# Sensors_Test.net
KiCad netlist of a schematic drawn in Altium Designer
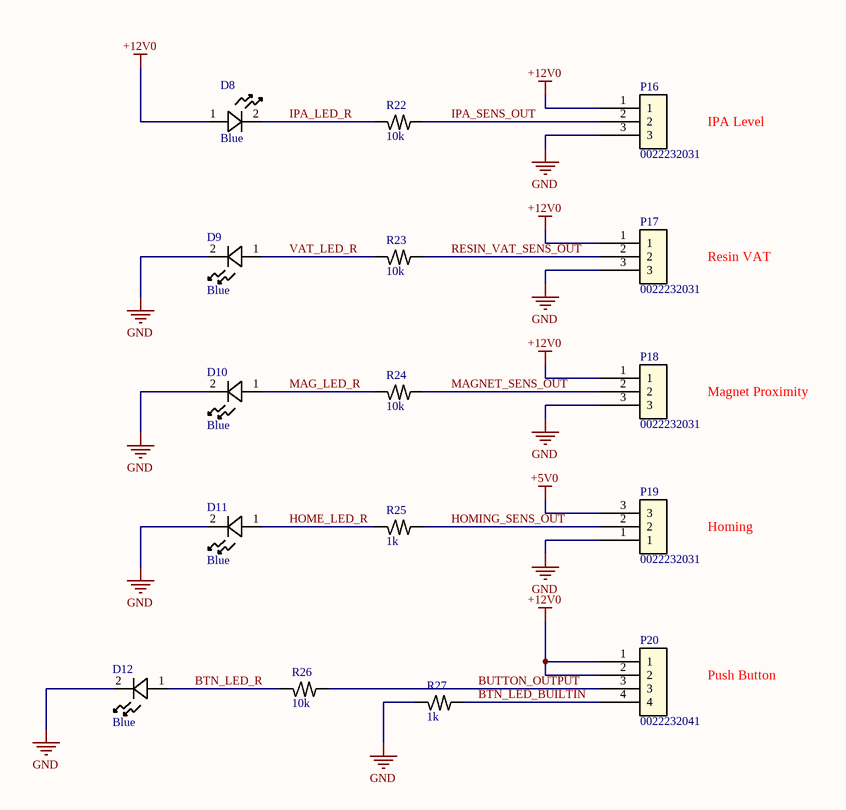
[diagram p0: Sensors Test.SchDoc]

(export (version "E")
  (design (tool "Eeschema 10.0.6"))
  (components
    (comp (ref "D8")
      (value "Blue")
      (footprint "LED0805 BLUE")
      (description "LED BLUE WATER CLEAR 0805 SMD")
      (fields (field (name "MF") "XINGLIGHT") (field (name "MP") "XL-TD2012UBC"))
      (libsource (lib "Components") (part "LED"))
    )
    (comp (ref "D9")
      (value "Blue")
      (footprint "LED0805 BLUE")
      (description "LED BLUE WATER CLEAR 0805 SMD")
      (fields (field (name "MF") "XINGLIGHT") (field (name "MP") "XL-TD2012UBC"))
      (libsource (lib "Components") (part "LED"))
    )
    (comp (ref "D10")
      (value "Blue")
      (footprint "LED0805 BLUE")
      (description "LED BLUE WATER CLEAR 0805 SMD")
      (fields (field (name "MF") "XINGLIGHT") (field (name "MP") "XL-TD2012UBC"))
      (libsource (lib "Components") (part "LED"))
    )
    (comp (ref "D11")
      (value "Blue")
      (footprint "LED0805 BLUE")
      (description "LED BLUE WATER CLEAR 0805 SMD")
      (fields (field (name "MF") "XINGLIGHT") (field (name "MP") "XL-TD2012UBC"))
      (libsource (lib "Components") (part "LED"))
    )
    (comp (ref "D12")
      (value "Blue")
      (footprint "LED0805 BLUE")
      (description "LED BLUE WATER CLEAR 0805 SMD")
      (fields (field (name "MF") "XINGLIGHT") (field (name "MP") "XL-TD2012UBC"))
      (libsource (lib "Components") (part "LED"))
    )
    (comp (ref "P16")
      (value "0022232031")
      (footprint "Signal3")
      (description "SignalConnector, 3 leads")
      (fields (field (name "MF") "Molex"))
      (libsource (lib "Connectors") (part "Signal3"))
    )
    (comp (ref "P17")
      (value "0022232031")
      (footprint "Signal3")
      (description "SignalConnector, 3 leads")
      (fields (field (name "MF") "Molex"))
      (libsource (lib "Connectors") (part "Signal3"))
    )
    (comp (ref "P18")
      (value "0022232031")
      (footprint "Signal3")
      (description "SignalConnector, 3 leads")
      (fields (field (name "MF") "Molex"))
      (libsource (lib "Connectors") (part "Signal3"))
    )
    (comp (ref "P19")
      (value "0022232031")
      (footprint "Signal3")
      (description "SignalConnector, 3 leads")
      (fields (field (name "MF") "Molex"))
      (libsource (lib "") (part "Signal3_1"))
    )
    (comp (ref "P20")
      (value "0022232041")
      (footprint "Signal4")
      (description "SignalConnector, 4 leads")
      (fields (field (name "MF") "Molex"))
      (libsource (lib "Connectors") (part "Signal4"))
    )
    (comp (ref "R22")
      (value "10k")
      (footprint "R0603")
      (description "RES 10kΩ ±1% 100mW 0603")
      (fields (field (name "MF") "FOJAN") (field (name "MP") "FRC0603F1002TS"))
      (libsource (lib "Components") (part "Res"))
    )
    (comp (ref "R23")
      (value "10k")
      (footprint "R0603")
      (description "RES 10kΩ ±1% 100mW 0603")
      (fields (field (name "MF") "FOJAN") (field (name "MP") "FRC0603F1002TS"))
      (libsource (lib "Components") (part "Res"))
    )
    (comp (ref "R24")
      (value "10k")
      (footprint "R0603")
      (description "RES 10kΩ ±1% 100mW 0603")
      (fields (field (name "MF") "FOJAN") (field (name "MP") "FRC0603F1002TS"))
      (libsource (lib "Components") (part "Res"))
    )
    (comp (ref "R25")
      (value "1k")
      (footprint "R0603")
      (description "RES 1kΩ ±5% 100mW 0603")
      (fields (field (name "MF") "VO") (field (name "MP") "SCR0603J1K"))
      (libsource (lib "Components") (part "Res"))
    )
    (comp (ref "R26")
      (value "10k")
      (footprint "R0603")
      (description "RES 10kΩ ±1% 100mW 0603")
      (fields (field (name "MF") "FOJAN") (field (name "MP") "FRC0603F1002TS"))
      (libsource (lib "Components") (part "Res"))
    )
    (comp (ref "R27")
      (value "1k")
      (footprint "R0603")
      (description "RES 1kΩ ±5% 100mW 0603")
      (fields (field (name "MF") "VO") (field (name "MP") "SCR0603J1K"))
      (libsource (lib "Components") (part "Res"))
    )
  )
  (nets
    (net (code "1") (name "+5V0") (class "Default")
      (node (ref "P19") (pin "3") (pinfunction "3_3") (pintype "passive"))
    )
    (net (code "2") (name "+12V0") (class "Default")
      (node (ref "D8") (pin "1") (pinfunction "1_1") (pintype "passive"))
      (node (ref "P16") (pin "1") (pinfunction "1_1") (pintype "passive"))
      (node (ref "P17") (pin "1") (pinfunction "1_1") (pintype "passive"))
      (node (ref "P18") (pin "1") (pinfunction "1_1") (pintype "passive"))
      (node (ref "P20") (pin "1") (pinfunction "1_1") (pintype "passive"))
      (node (ref "P20") (pin "2") (pinfunction "2_2") (pintype "passive"))
    )
    (net (code "3") (name "/BTN_LED_BUILTIN") (class "Default")
      (node (ref "P20") (pin "4") (pinfunction "4_4") (pintype "passive"))
      (node (ref "R27") (pin "1") (pinfunction "1_1") (pintype "passive"))
    )
    (net (code "4") (name "/BTN_LED_R") (class "Default")
      (node (ref "D12") (pin "1") (pinfunction "1_1") (pintype "passive"))
      (node (ref "R26") (pin "2") (pinfunction "2_2") (pintype "passive"))
    )
    (net (code "5") (name "/BUTTON_OUTPUT") (class "Default")
      (node (ref "P20") (pin "3") (pinfunction "3_3") (pintype "passive"))
      (node (ref "R26") (pin "1") (pinfunction "1_1") (pintype "passive"))
    )
    (net (code "6") (name "/HOME_LED_R") (class "Default")
      (node (ref "D11") (pin "1") (pinfunction "1_1") (pintype "passive"))
      (node (ref "R25") (pin "2") (pinfunction "2_2") (pintype "passive"))
    )
    (net (code "7") (name "/HOMING_SENS_OUT") (class "Default")
      (node (ref "P19") (pin "2") (pinfunction "2_2") (pintype "passive"))
      (node (ref "R25") (pin "1") (pinfunction "1_1") (pintype "passive"))
    )
    (net (code "8") (name "/IPA_LED_R") (class "Default")
      (node (ref "D8") (pin "2") (pinfunction "2_2") (pintype "passive"))
      (node (ref "R22") (pin "2") (pinfunction "2_2") (pintype "passive"))
    )
    (net (code "9") (name "/IPA_SENS_OUT") (class "Default")
      (node (ref "P16") (pin "2") (pinfunction "2_2") (pintype "passive"))
      (node (ref "R22") (pin "1") (pinfunction "1_1") (pintype "passive"))
    )
    (net (code "10") (name "/MAGNET_SENS_OUT") (class "Default")
      (node (ref "P18") (pin "2") (pinfunction "2_2") (pintype "passive"))
      (node (ref "R24") (pin "1") (pinfunction "1_1") (pintype "passive"))
    )
    (net (code "11") (name "/MAG_LED_R") (class "Default")
      (node (ref "D10") (pin "1") (pinfunction "1_1") (pintype "passive"))
      (node (ref "R24") (pin "2") (pinfunction "2_2") (pintype "passive"))
    )
    (net (code "12") (name "/RESIN_VAT_SENS_OUT") (class "Default")
      (node (ref "P17") (pin "2") (pinfunction "2_2") (pintype "passive"))
      (node (ref "R23") (pin "1") (pinfunction "1_1") (pintype "passive"))
    )
    (net (code "13") (name "/VAT_LED_R") (class "Default")
      (node (ref "D9") (pin "1") (pinfunction "1_1") (pintype "passive"))
      (node (ref "R23") (pin "2") (pinfunction "2_2") (pintype "passive"))
    )
    (net (code "14") (name "GND") (class "Default")
      (node (ref "D10") (pin "2") (pinfunction "2_2") (pintype "passive"))
      (node (ref "D11") (pin "2") (pinfunction "2_2") (pintype "passive"))
      (node (ref "D12") (pin "2") (pinfunction "2_2") (pintype "passive"))
      (node (ref "D9") (pin "2") (pinfunction "2_2") (pintype "passive"))
      (node (ref "P16") (pin "3") (pinfunction "3_3") (pintype "passive"))
      (node (ref "P17") (pin "3") (pinfunction "3_3") (pintype "passive"))
      (node (ref "P18") (pin "3") (pinfunction "3_3") (pintype "passive"))
      (node (ref "P19") (pin "1") (pinfunction "1_1") (pintype "passive"))
      (node (ref "R27") (pin "2") (pinfunction "2_2") (pintype "passive"))
    )
  )
)
